# power_supply.net
KiCad netlist of a schematic drawn in Altium Designer
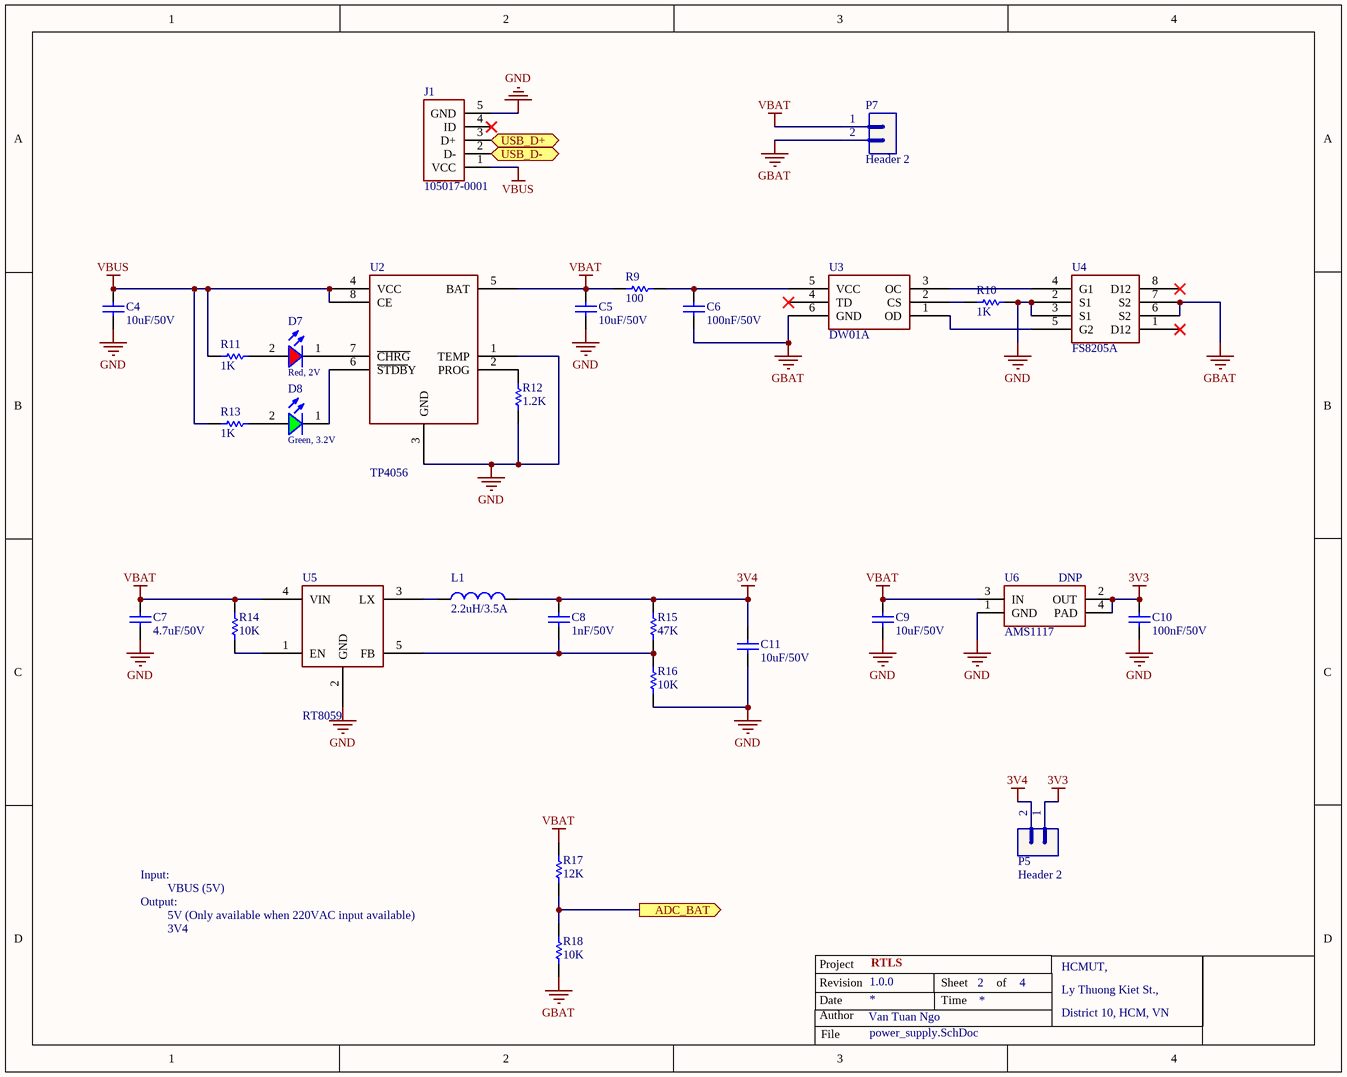
[diagram p0: power_supply.SchDoc]

(export (version "E")
  (design (tool "Eeschema 10.0.6"))
  (components
    (comp (ref "C4")
      (value "10uF/50V")
      (footprint "CAP-SM-0805")
      (description "CAP CER 10UF 50V X5R 0805")
      (fields
        (field (name "MANUFACTURER") "Yageo")
        (field (name "MANUFACTURER PART NUMBER") "CC0805KKX5R9BB106")
      )
      (libsource (lib "capacitor-smd") (part "Cap-10uF-50V-0805"))
    )
    (comp (ref "C5")
      (value "10uF/50V")
      (footprint "CAP-SM-0805")
      (description "CAP CER 10UF 50V X5R 0805")
      (fields
        (field (name "MANUFACTURER") "Yageo")
        (field (name "MANUFACTURER PART NUMBER") "CC0805KKX5R9BB106")
      )
      (libsource (lib "capacitor-smd") (part "Cap-10uF-50V-0805"))
    )
    (comp (ref "C6")
      (value "100nF/50V")
      (footprint "CAP-SM-0805")
      (description "CAP CER 0.1UF 50V Y5V 0805")
      (fields
        (field (name "MANUFACTURER") "Samsung Electro-Mechanics")
        (field (name "MANUFACTURER PART NUMBER") "CL21F104ZBCNNNC")
      )
      (libsource (lib "capacitor-smd") (part "Cap-100nF-50V-0805"))
    )
    (comp (ref "C7")
      (value "4.7uF/50V")
      (footprint "CAP-SM-0805")
      (description "CAP CER 4.7UF 50V X5R 0805")
      (fields
        (field (name "MANUFACTURER") "Murata Electronics")
        (field (name "MANUFACTURER PART NUMBER") "GRM21BR61H475KE51L")
      )
      (libsource (lib "capacitor-smd") (part "Cap-4.7uF-50V-0805"))
    )
    (comp (ref "C8")
      (value "1nF/50V")
      (footprint "CAP-SM-0805")
      (description "CAP CER 22PF 100V X7R 0805")
      (fields
        (field (name "MANUFACTURER") "Johanson Dielectrics Inc.")
        (field (name "MANUFACTURER PART NUMBER") "101X15W102MV4E")
      )
      (libsource (lib "capacitor-smd") (part "Cap-22pF-50V-0805"))
    )
    (comp (ref "C9")
      (value "10uF/50V")
      (footprint "CAP-SM-0805")
      (description "CAP CER 10UF 50V X5R 0805")
      (fields
        (field (name "MANUFACTURER") "Yageo")
        (field (name "MANUFACTURER PART NUMBER") "CC0805KKX5R9BB106")
      )
      (libsource (lib "capacitor-smd") (part "Cap-10uF-50V-0805"))
    )
    (comp (ref "C10")
      (value "100nF/50V")
      (footprint "CAP-SM-0805")
      (description "CAP CER 0.1UF 50V Y5V 0805")
      (fields
        (field (name "MANUFACTURER") "Samsung Electro-Mechanics")
        (field (name "MANUFACTURER PART NUMBER") "CL21F104ZBCNNNC")
      )
      (libsource (lib "capacitor-smd") (part "Cap-100nF-50V-0805"))
    )
    (comp (ref "C11")
      (value "10uF/50V")
      (footprint "CAP-SM-0805")
      (description "CAP CER 10UF 50V X5R 0805")
      (fields
        (field (name "MANUFACTURER") "Yageo")
        (field (name "MANUFACTURER PART NUMBER") "CC0805KKX5R9BB106")
      )
      (libsource (lib "capacitor-smd") (part "Cap-10uF-50V-0805"))
    )
    (comp (ref "D7")
      (value "Red, 2V")
      (footprint "WL-SMCW_0805")
      (description "WL-SMCW SMT Mono-color Chip LED Waterclear, size 0805, Red, 2V, 140deg")
      (fields (field (name "PART NUMBER") "150080RS75000") (field (name "PUBLISHER") "Wurth Elektronik"))
      (libsource (lib "led-smd-0805") (part "150080RS75000"))
    )
    (comp (ref "D8")
      (value "Green, 3.2V")
      (footprint "WL-SMCW_0805")
      (description "WL-SMCW SMT Mono-color Chip LED Waterclear, size 0805, Green, 3.2V, 140deg")
      (fields (field (name "PART NUMBER") "150080GS75000") (field (name "PUBLISHER") "Wurth Elektronik"))
      (libsource (lib "led-smd-0805") (part "150080GS75000"))
    )
    (comp (ref "J1")
      (value "105017-0001")
      (footprint "Micro-USB-Female")
      (description "CONN RCPT USB2.0 MICRO B SMD R/A")
      (fields
        (field (name "LOCAL SUPPLIER PART NUMBER") "x")
        (field (name "COPYRIGHT") "Copyright (C) 2018 Accelerated Designs. All rights reserved")
      )
      (libsource (lib "header-connector") (part "Micro-USB-Female"))
    )
    (comp (ref "L1")
      (value "2.2uH/3.5A")
      (footprint "CD53")
      (libsource (lib "inductor-smd") (part "ind-2.2uH-3.5A-CD53"))
    )
    (comp (ref "P5")
      (value "Header 2")
      (footprint "JP2")
      (description "Header, 2-Pin")
      (fields (field (name "LOCAL SUPPLIER PART NUMBER") "x") (field (name "PUBLISHER") "Altium Limited"))
      (libsource (lib "header-connector") (part "Header 2"))
    )
    (comp (ref "P7")
      (value "Header 2")
      (footprint "JP2")
      (description "Header, 2-Pin")
      (fields (field (name "LOCAL SUPPLIER PART NUMBER") "x") (field (name "PUBLISHER") "Altium Limited"))
      (libsource (lib "") (part "Header 2_1"))
    )
    (comp (ref "R9")
      (value "100")
      (footprint "resistor-smd:RES-SM-0805")
      (description "RES 100 OHM 0.1% 1/5W 0805")
      (fields
        (field (name "MANUFACTURER") "Vishay Thin Film")
        (field (name "MANUFACTURER PART NUMBER") "PTN0805E10R0BST1")
      )
      (libsource (lib "resistor-smd") (part "Res-100-0805"))
    )
    (comp (ref "R10")
      (value "1K")
      (footprint "resistor-smd:RES-SM-0805")
      (description "RES 1K OHM 1% 1/4W 0805")
      (fields
        (field (name "MANUFACTURER") "Stackpole Electronics Inc")
        (field (name "MANUFACTURER PART NUMBER") "RNCP0805FTD1K00")
      )
      (libsource (lib "resistor-smd") (part "Res-1K-0805"))
    )
    (comp (ref "R11")
      (value "1K")
      (footprint "resistor-smd:RES-SM-0805")
      (description "RES 1K OHM 1% 1/4W 0805")
      (fields
        (field (name "MANUFACTURER") "Stackpole Electronics Inc")
        (field (name "MANUFACTURER PART NUMBER") "RNCP0805FTD1K00")
      )
      (libsource (lib "resistor-smd") (part "Res-1K-0805"))
    )
    (comp (ref "R12")
      (value "1.2K")
      (footprint "resistor-smd:RES-SM-0805")
      (description "RES SMD 1.2K OHM 1% 1/8W 0805")
      (fields
        (field (name "MANUFACTURER") "TE Connectivity Passive Product")
        (field (name "MANUFACTURER PART NUMBER") "CRG0805F1K2")
      )
      (libsource (lib "resistor-smd") (part "Res-1.2K-0805"))
    )
    (comp (ref "R13")
      (value "1K")
      (footprint "resistor-smd:RES-SM-0805")
      (description "RES 1K OHM 1% 1/4W 0805")
      (fields
        (field (name "MANUFACTURER") "Stackpole Electronics Inc")
        (field (name "MANUFACTURER PART NUMBER") "RNCP0805FTD1K00")
      )
      (libsource (lib "resistor-smd") (part "Res-1K-0805"))
    )
    (comp (ref "R14")
      (value "10K")
      (footprint "resistor-smd:RES-SM-0805")
      (description "RES 10K OHM 1% 1/4W 0805")
      (fields
        (field (name "MANUFACTURER") "Stackpole Electronics Inc")
        (field (name "MANUFACTURER PART NUMBER") "RNCP0805FTD10K0")
      )
      (libsource (lib "resistor-smd") (part "Res-10k-0805"))
    )
    (comp (ref "R15")
      (value "47K")
      (footprint "resistor-smd:RES-SM-0805")
      (description "RES SMD 47K OHM 1% 1/8W 0805")
      (fields
        (field (name "MANUFACTURER") "Yageo")
        (field (name "MANUFACTURER PART NUMBER") "RC0805FR-0747KL")
      )
      (libsource (lib "resistor-smd") (part "Res-47K-0805"))
    )
    (comp (ref "R16")
      (value "10K")
      (footprint "resistor-smd:RES-SM-0805")
      (description "RES 10K OHM 1% 1/4W 0805")
      (fields
        (field (name "MANUFACTURER") "Stackpole Electronics Inc")
        (field (name "MANUFACTURER PART NUMBER") "RNCP0805FTD10K0")
      )
      (libsource (lib "resistor-smd") (part "Res-10k-0805"))
    )
    (comp (ref "R17")
      (value "12K")
      (footprint "resistor-smd:RES-SM-0805")
      (description "RES 12 KOHM JUMPER 0805")
      (fields
        (field (name "MANUFACTURER") "Vishay Thin Film")
        (field (name "MANUFACTURER PART NUMBER") "PAT0805E3121BST1")
      )
      (libsource (lib "resistor-smd") (part "Res-12K-0805"))
    )
    (comp (ref "R18")
      (value "10K")
      (footprint "resistor-smd:RES-SM-0805")
      (description "RES 10K OHM 1% 1/4W 0805")
      (fields
        (field (name "MANUFACTURER") "Stackpole Electronics Inc")
        (field (name "MANUFACTURER PART NUMBER") "RNCP0805FTD10K0")
      )
      (libsource (lib "resistor-smd") (part "Res-10k-0805"))
    )
    (comp (ref "U2")
      (value "TP4056")
      (footprint "SOP8")
      (description "Linear charger for single cell\r\nlithium-ion batteries")
      (libsource (lib "power-ic-module") (part "TP4056"))
    )
    (comp (ref "U3")
      (value "DW01A")
      (footprint "SOT-23-6")
      (description "Battery protection IC")
      (libsource (lib "power-ic-module") (part "DW01A"))
    )
    (comp (ref "U4") (value "FS8205A") (footprint "TSSOP8") (libsource (lib "mosfet-smd") (part "FS8205A")))
    (comp (ref "U5")
      (value "RT8059")
      (footprint "SOT-23-5")
      (description "High efficiency PWM step-down DC/DC converter")
      (libsource (lib "power-ic-module") (part "RT8059"))
    )
    (comp (ref "U6")
      (value "AMS1117")
      (footprint "SOT223")
      (description "Available in 1.8V, 2.5V, 2.85V, 3.3V, 5V, and  Adjustable Versions")
      (libsource (lib "power-ic-module") (part "AMS1117"))
    )
  )
  (nets
    (net (code "1") (name "/ADC_BAT") (class "Default")
      (node (ref "R17") (pin "1") (pinfunction "1_1") (pintype "passive"))
      (node (ref "R18") (pin "2") (pinfunction "2_2") (pintype "passive"))
    )
    (net (code "2") (name "/USB_D+") (class "Default")
      (node (ref "J1") (pin "3") (pinfunction "D+_3") (pintype "passive"))
    )
    (net (code "3") (name "/USB_D-") (class "Default")
      (node (ref "J1") (pin "2") (pinfunction "D-_2") (pintype "passive"))
    )
    (net (code "4") (name "3V3") (class "Default")
      (node (ref "C10") (pin "2") (pinfunction "2_2") (pintype "passive"))
      (node (ref "P5") (pin "1") (pinfunction "1_1") (pintype "passive"))
      (node (ref "U6") (pin "2") (pinfunction "OUT_2") (pintype "passive"))
      (node (ref "U6") (pin "4") (pinfunction "PAD_4") (pintype "passive"))
    )
    (net (code "5") (name "3V4") (class "Default")
      (node (ref "C11") (pin "2") (pinfunction "2_2") (pintype "passive"))
      (node (ref "C8") (pin "2") (pinfunction "2_2") (pintype "passive"))
      (node (ref "L1") (pin "2") (pinfunction "2_2") (pintype "passive"))
      (node (ref "P5") (pin "2") (pinfunction "2_2") (pintype "passive"))
      (node (ref "R15") (pin "2") (pinfunction "2_2") (pintype "passive"))
    )
    (net (code "6") (name "GBAT") (class "Default")
      (node (ref "C6") (pin "1") (pinfunction "1_1") (pintype "passive"))
      (node (ref "P7") (pin "2") (pinfunction "2_2") (pintype "passive"))
      (node (ref "R18") (pin "1") (pinfunction "1_1") (pintype "passive"))
      (node (ref "U3") (pin "6") (pinfunction "GND_6") (pintype "passive"))
      (node (ref "U4") (pin "6") (pinfunction "S2_6") (pintype "passive"))
      (node (ref "U4") (pin "7") (pinfunction "S2_7") (pintype "passive"))
    )
    (net (code "7") (name "GND") (class "Default")
      (node (ref "C10") (pin "1") (pinfunction "1_1") (pintype "passive"))
      (node (ref "C11") (pin "1") (pinfunction "1_1") (pintype "passive"))
      (node (ref "C4") (pin "1") (pinfunction "1_1") (pintype "passive"))
      (node (ref "C5") (pin "1") (pinfunction "1_1") (pintype "passive"))
      (node (ref "C7") (pin "1") (pinfunction "1_1") (pintype "passive"))
      (node (ref "C9") (pin "1") (pinfunction "1_1") (pintype "passive"))
      (node (ref "J1") (pin "5") (pinfunction "GND_5") (pintype "passive"))
      (node (ref "R10") (pin "2") (pinfunction "2_2") (pintype "passive"))
      (node (ref "R12") (pin "1") (pinfunction "1_1") (pintype "passive"))
      (node (ref "R16") (pin "1") (pinfunction "1_1") (pintype "passive"))
      (node (ref "U2") (pin "1") (pinfunction "TEMP_1") (pintype "passive"))
      (node (ref "U2") (pin "3") (pinfunction "GND_3") (pintype "passive"))
      (node (ref "U4") (pin "2") (pinfunction "S1_2") (pintype "passive"))
      (node (ref "U4") (pin "3") (pinfunction "S1_3") (pintype "passive"))
      (node (ref "U5") (pin "2") (pinfunction "GND_2") (pintype "passive"))
      (node (ref "U6") (pin "1") (pinfunction "GND_1") (pintype "passive"))
    )
    (net (code "8") (name "Net-(D7-A)") (class "Default")
      (node (ref "D7") (pin "2") (pinfunction "A_2") (pintype "passive"))
      (node (ref "R11") (pin "2") (pinfunction "2_2") (pintype "passive"))
    )
    (net (code "9") (name "Net-(D7-K)") (class "Default")
      (node (ref "D7") (pin "1") (pinfunction "K_1") (pintype "passive"))
      (node (ref "U2") (pin "7") (pinfunction "~{CHRG}_7") (pintype "passive"))
    )
    (net (code "10") (name "Net-(D8-A)") (class "Default")
      (node (ref "D8") (pin "2") (pinfunction "A_2") (pintype "passive"))
      (node (ref "R13") (pin "2") (pinfunction "2_2") (pintype "passive"))
    )
    (net (code "11") (name "Net-(D8-K)") (class "Default")
      (node (ref "D8") (pin "1") (pinfunction "K_1") (pintype "passive"))
      (node (ref "U2") (pin "6") (pinfunction "~{STDB}Y_6") (pintype "passive"))
    )
    (net (code "12") (name "Net-(U2-PROG)") (class "Default")
      (node (ref "R12") (pin "2") (pinfunction "2_2") (pintype "passive"))
      (node (ref "U2") (pin "2") (pinfunction "PROG_2") (pintype "passive"))
    )
    (net (code "13") (name "Net-(U3-CS)") (class "Default")
      (node (ref "R10") (pin "1") (pinfunction "1_1") (pintype "passive"))
      (node (ref "U3") (pin "2") (pinfunction "CS_2") (pintype "passive"))
    )
    (net (code "14") (name "Net-(U3-OC)") (class "Default")
      (node (ref "U3") (pin "3") (pinfunction "OC_3") (pintype "passive"))
      (node (ref "U4") (pin "4") (pinfunction "G1_4") (pintype "passive"))
    )
    (net (code "15") (name "Net-(U3-OD)") (class "Default")
      (node (ref "U3") (pin "1") (pinfunction "OD_1") (pintype "passive"))
      (node (ref "U4") (pin "5") (pinfunction "G2_5") (pintype "passive"))
    )
    (net (code "16") (name "Net-(U3-VCC)") (class "Default")
      (node (ref "C6") (pin "2") (pinfunction "2_2") (pintype "passive"))
      (node (ref "R9") (pin "2") (pinfunction "2_2") (pintype "passive"))
      (node (ref "U3") (pin "5") (pinfunction "VCC_5") (pintype "passive"))
    )
    (net (code "17") (name "Net-(U5-EN)") (class "Default")
      (node (ref "R14") (pin "1") (pinfunction "1_1") (pintype "passive"))
      (node (ref "U5") (pin "1") (pinfunction "EN_1") (pintype "passive"))
    )
    (net (code "18") (name "Net-(U5-FB)") (class "Default")
      (node (ref "C8") (pin "1") (pinfunction "1_1") (pintype "passive"))
      (node (ref "R15") (pin "1") (pinfunction "1_1") (pintype "passive"))
      (node (ref "R16") (pin "2") (pinfunction "2_2") (pintype "passive"))
      (node (ref "U5") (pin "5") (pinfunction "FB_5") (pintype "passive"))
    )
    (net (code "19") (name "Net-(U5-LX)") (class "Default")
      (node (ref "L1") (pin "1") (pinfunction "1_1") (pintype "passive"))
      (node (ref "U5") (pin "3") (pinfunction "LX_3") (pintype "passive"))
    )
    (net (code "20") (name "VBAT") (class "Default")
      (node (ref "C5") (pin "2") (pinfunction "2_2") (pintype "passive"))
      (node (ref "C7") (pin "2") (pinfunction "2_2") (pintype "passive"))
      (node (ref "C9") (pin "2") (pinfunction "2_2") (pintype "passive"))
      (node (ref "P7") (pin "1") (pinfunction "1_1") (pintype "passive"))
      (node (ref "R14") (pin "2") (pinfunction "2_2") (pintype "passive"))
      (node (ref "R17") (pin "2") (pinfunction "2_2") (pintype "passive"))
      (node (ref "R9") (pin "1") (pinfunction "1_1") (pintype "passive"))
      (node (ref "U2") (pin "5") (pinfunction "BAT_5") (pintype "passive"))
      (node (ref "U5") (pin "4") (pinfunction "VIN_4") (pintype "passive"))
      (node (ref "U6") (pin "3") (pinfunction "IN_3") (pintype "passive"))
    )
    (net (code "21") (name "VBUS") (class "Default")
      (node (ref "C4") (pin "2") (pinfunction "2_2") (pintype "passive"))
      (node (ref "J1") (pin "1") (pinfunction "VCC_1") (pintype "power_in"))
      (node (ref "R11") (pin "1") (pinfunction "1_1") (pintype "passive"))
      (node (ref "R13") (pin "1") (pinfunction "1_1") (pintype "passive"))
      (node (ref "U2") (pin "4") (pinfunction "VCC_4") (pintype "passive"))
      (node (ref "U2") (pin "8") (pinfunction "CE_8") (pintype "passive"))
    )
    (net (code "22") (name "unconnected-(J1-ID-Pad4)") (class "Default")
      (node (ref "J1") (pin "4") (pinfunction "ID_4") (pintype "passive+no_connect"))
    )
    (net (code "23") (name "unconnected-(U3-TD-Pad4)") (class "Default")
      (node (ref "U3") (pin "4") (pinfunction "TD_4") (pintype "passive+no_connect"))
    )
    (net (code "24") (name "unconnected-(U4-D12-Pad1)") (class "Default")
      (node (ref "U4") (pin "1") (pinfunction "D12_1") (pintype "passive+no_connect"))
    )
    (net (code "25") (name "unconnected-(U4-D12-Pad8)") (class "Default")
      (node (ref "U4") (pin "8") (pinfunction "D12_8") (pintype "passive+no_connect"))
    )
  )
)
